# telem_board.net
KiCad netlist of a schematic drawn in EAGLE
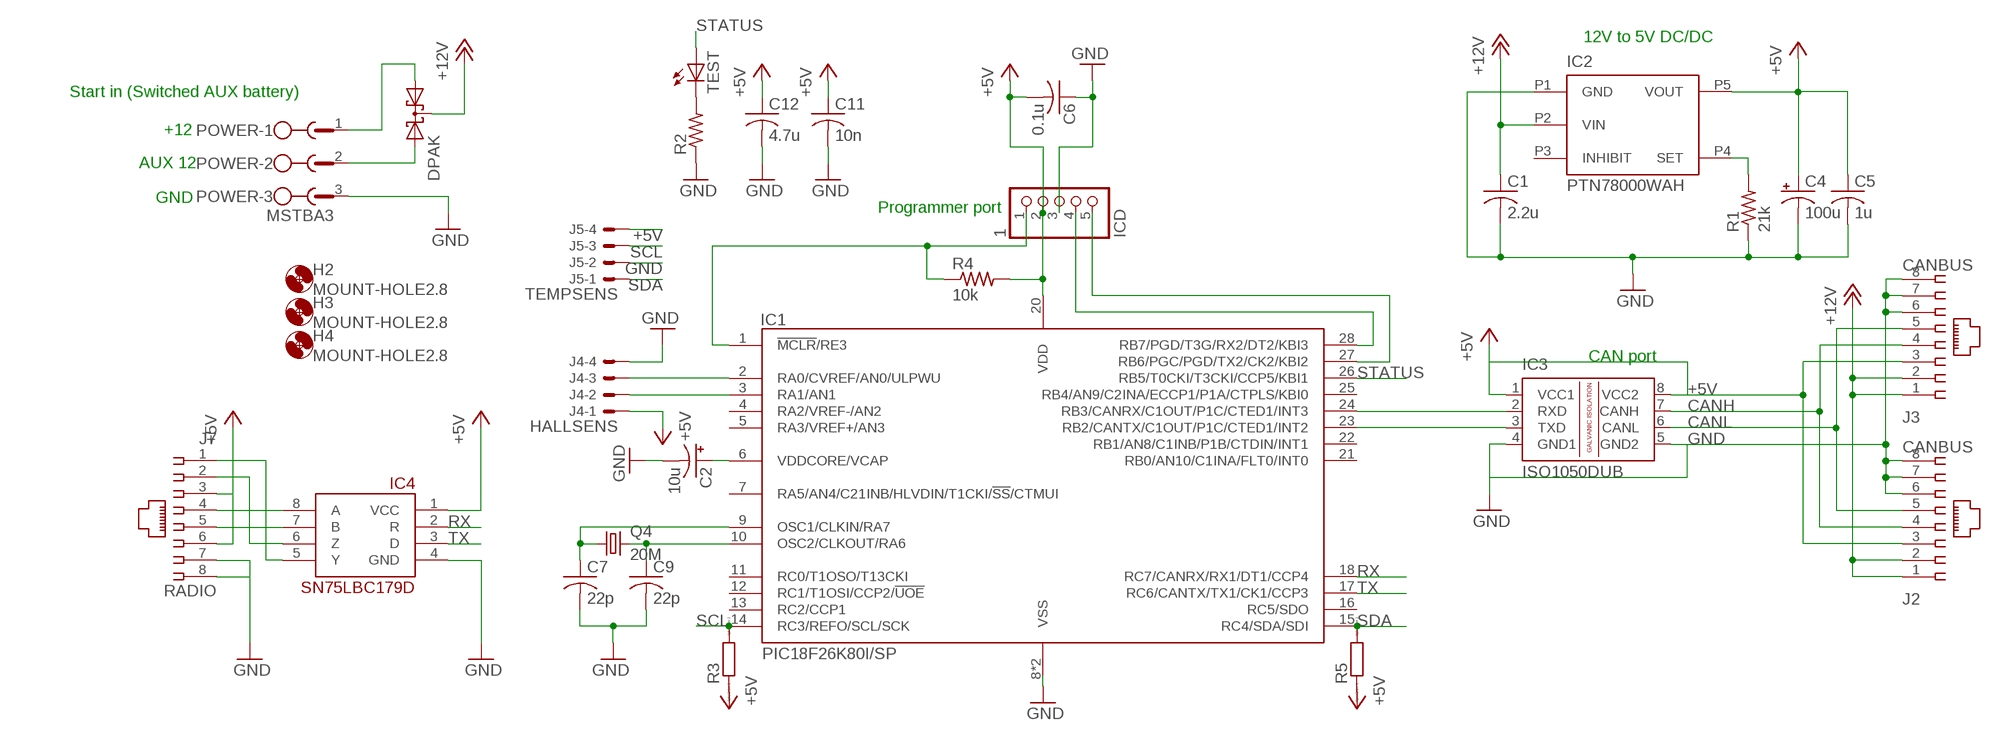
[diagram p0: schematic, sheet 1]

(export (version "E")
  (design (tool "Eeschema 10.0.6"))
  (components
    (comp (ref "1")
      (value "ICD")
      (footprint "eagle-import:1X05")
      (libsource (lib "eagle-import") (part "PINHD-1X5"))
    )
    (comp (ref "C1")
      (value "2.2u")
      (footprint "eagle-import:C1206")
      (libsource (lib "eagle-import") (part "C-USC1206"))
    )
    (comp (ref "C2")
      (value "10u")
      (footprint "eagle-import:TT2D4")
      (libsource (lib "eagle-import") (part "CPOL-USTT2D4"))
    )
    (comp (ref "C4")
      (value "100u")
      (footprint "eagle-import:SMC_D")
      (libsource (lib "eagle-import") (part "CPOL-USSMCD"))
    )
    (comp (ref "C5")
      (value "1u")
      (footprint "eagle-import:C0805")
      (libsource (lib "eagle-import") (part "C-USC0805"))
    )
    (comp (ref "C6")
      (value "0.1u")
      (footprint "eagle-import:C0805")
      (libsource (lib "eagle-import") (part "C-USC0805"))
    )
    (comp (ref "C7")
      (value "22p")
      (footprint "eagle-import:C0805")
      (libsource (lib "eagle-import") (part "C-USC0805"))
    )
    (comp (ref "C9")
      (value "22p")
      (footprint "eagle-import:C0805")
      (libsource (lib "eagle-import") (part "C-USC0805"))
    )
    (comp (ref "C11")
      (value "10n")
      (footprint "eagle-import:C0805")
      (libsource (lib "eagle-import") (part "resistor_C-USC0805"))
    )
    (comp (ref "C12")
      (value "4.7u")
      (footprint "eagle-import:C0805")
      (libsource (lib "eagle-import") (part "resistor_C-USC0805"))
    )
    (comp (ref "DPAK")
      (value "DIODE_2SCHOTTKY-DPAK")
      (footprint "eagle-import:DPAK")
      (libsource (lib "eagle-import") (part "DIODE_2SCHOTTKY-DPAK"))
    )
    (comp (ref "H2")
      (value "MOUNT-HOLE2.8")
      (footprint "eagle-import:2,8")
      (libsource (lib "eagle-import") (part "MOUNT-HOLE2.8"))
    )
    (comp (ref "H3")
      (value "MOUNT-HOLE2.8")
      (footprint "eagle-import:2,8")
      (libsource (lib "eagle-import") (part "MOUNT-HOLE2.8"))
    )
    (comp (ref "H4")
      (value "MOUNT-HOLE2.8")
      (footprint "eagle-import:2,8")
      (libsource (lib "eagle-import") (part "MOUNT-HOLE2.8"))
    )
    (comp (ref "IC1")
      (value "PIC18F26K80I/SP")
      (footprint "eagle-import:DIL28_3")
      (libsource (lib "eagle-import") (part "PIC18F26K80I/SP"))
    )
    (comp (ref "IC2")
      (value "PTN78000WAH")
      (footprint "eagle-import:PTN78000")
      (libsource (lib "eagle-import") (part "PTN78000WAH"))
    )
    (comp (ref "IC3")
      (value "ISO1050DUB")
      (footprint "eagle-import:DUB-R-PDSO-G8")
      (fields (field (name "MPN") "ISO1050DUBR"))
      (libsource (lib "eagle-import") (part "ISO1050DUB"))
    )
    (comp (ref "IC4")
      (value "SN75LBC179D")
      (footprint "eagle-import:SO08")
      (libsource (lib "eagle-import") (part "SN75LBC179D"))
    )
    (comp (ref "J2")
      (value "CANBUS")
      (footprint "eagle-import:215877-7")
      (libsource (lib "eagle-import") (part "215877-7"))
    )
    (comp (ref "J3")
      (value "CANBUS")
      (footprint "eagle-import:215877-7")
      (libsource (lib "eagle-import") (part "215877-7"))
    )
    (comp (ref "J4")
      (value "HALLSENS")
      (footprint "eagle-import:6410-04")
      (libsource (lib "eagle-import") (part "22-?-0427-2041"))
    )
    (comp (ref "J5")
      (value "TEMPSENS")
      (footprint "eagle-import:6410-04")
      (libsource (lib "eagle-import") (part "22-?-0427-2041"))
    )
    (comp (ref "J7")
      (value "RADIO")
      (footprint "eagle-import:215877-7")
      (libsource (lib "eagle-import") (part "215877-7"))
    )
    (comp (ref "POWER")
      (value "MSTBA3")
      (footprint "eagle-import:MSTBA3")
      (fields (field (name "MF") "FARNELL") (field (name "MPN") "1757255"))
      (libsource (lib "eagle-import") (part "MSTBA3"))
    )
    (comp (ref "Q4")
      (value "20M")
      (footprint "eagle-import:HC49_S")
      (libsource (lib "eagle-import") (part "CRYSTALHC49S"))
    )
    (comp (ref "R1")
      (value "21k")
      (footprint "eagle-import:R0805")
      (libsource (lib "eagle-import") (part "rcl_R-US_R0805"))
    )
    (comp (ref "R2")
      (value "R-US_R0805")
      (footprint "eagle-import:R0805")
      (libsource (lib "eagle-import") (part "R-US_R0805"))
    )
    (comp (ref "R3") (value "R") (footprint "eagle-import:R0805") (libsource (lib "eagle-import") (part "R")))
    (comp (ref "R4")
      (value "10k")
      (footprint "eagle-import:R0805")
      (libsource (lib "eagle-import") (part "rcl_R-US_R0805"))
    )
    (comp (ref "R5") (value "R") (footprint "eagle-import:R0805") (libsource (lib "eagle-import") (part "R")))
    (comp (ref "TEST")
      (value "LEDCHIP-LED0805")
      (footprint "eagle-import:CHIP-LED0805")
      (libsource (lib "eagle-import") (part "LEDCHIP-LED0805"))
    )
  )
  (nets
    (net (code "1") (name "+5V") (class "Default")
      (node (ref "1") (pin "2") (pinfunction "2_2") (pintype "passive"))
      (node (ref "C11") (pin "1") (pinfunction "1_1") (pintype "passive"))
      (node (ref "C12") (pin "1") (pinfunction "1_1") (pintype "passive"))
      (node (ref "C4") (pin "+") (pinfunction "+_+") (pintype "passive"))
      (node (ref "C5") (pin "1") (pinfunction "1_1") (pintype "passive"))
      (node (ref "C6") (pin "2") (pinfunction "2_2") (pintype "passive"))
      (node (ref "IC1") (pin "20") (pinfunction "VDD_20") (pintype "power_in"))
      (node (ref "IC2") (pin "P5") (pinfunction "VOUT_P5") (pintype "power_in"))
      (node (ref "IC3") (pin "1") (pinfunction "VCC1_1") (pintype "input"))
      (node (ref "IC3") (pin "8") (pinfunction "VCC2_8") (pintype "input"))
      (node (ref "IC4") (pin "1") (pinfunction "VCC_1") (pintype "power_in"))
      (node (ref "J2") (pin "3") (pinfunction "3_3") (pintype "passive"))
      (node (ref "J3") (pin "3") (pinfunction "3_3") (pintype "passive"))
      (node (ref "J4") (pin "1") (pinfunction "S_1") (pintype "passive"))
      (node (ref "J5") (pin "4") (pinfunction "S_4") (pintype "passive"))
      (node (ref "J7") (pin "3") (pinfunction "3_3") (pintype "passive"))
      (node (ref "J7") (pin "6") (pinfunction "6_6") (pintype "passive"))
      (node (ref "R3") (pin "1") (pinfunction "1_1") (pintype "passive"))
      (node (ref "R4") (pin "2") (pinfunction "2_2") (pintype "passive"))
      (node (ref "R5") (pin "1") (pinfunction "1_1") (pintype "passive"))
    )
    (net (code "2") (name "+12V") (class "Default")
      (node (ref "C1") (pin "1") (pinfunction "1_1") (pintype "passive"))
      (node (ref "DPAK") (pin "3") (pinfunction "C_3") (pintype "passive"))
      (node (ref "IC2") (pin "P2") (pinfunction "VIN_P2") (pintype "power_in"))
      (node (ref "J2") (pin "1") (pinfunction "1_1") (pintype "passive"))
      (node (ref "J2") (pin "2") (pinfunction "2_2") (pintype "passive"))
      (node (ref "J3") (pin "1") (pinfunction "1_1") (pintype "passive"))
      (node (ref "J3") (pin "2") (pinfunction "2_2") (pintype "passive"))
    )
    (net (code "3") (name "/CANH") (class "Default")
      (node (ref "IC3") (pin "7") (pinfunction "CANH_7") (pintype "input"))
      (node (ref "J2") (pin "4") (pinfunction "4_4") (pintype "passive"))
      (node (ref "J3") (pin "4") (pinfunction "4_4") (pintype "passive"))
    )
    (net (code "4") (name "/CANL") (class "Default")
      (node (ref "IC3") (pin "6") (pinfunction "CANL_6") (pintype "input"))
      (node (ref "J2") (pin "5") (pinfunction "5_5") (pintype "passive"))
      (node (ref "J3") (pin "5") (pinfunction "5_5") (pintype "passive"))
    )
    (net (code "5") (name "/RX") (class "Default")
      (node (ref "IC1") (pin "18") (pinfunction "RC7/CANRX/RX1/DT1/CCP4_18") (pintype "bidirectional"))
      (node (ref "IC4") (pin "2") (pinfunction "R_2") (pintype "output"))
    )
    (net (code "6") (name "/SCL") (class "Default")
      (node (ref "IC1") (pin "14") (pinfunction "RC3/REFO/SCL/SCK_14") (pintype "bidirectional"))
      (node (ref "J5") (pin "3") (pinfunction "S_3") (pintype "passive"))
      (node (ref "R3") (pin "2") (pinfunction "2_2") (pintype "passive"))
    )
    (net (code "7") (name "/SDA") (class "Default")
      (node (ref "IC1") (pin "15") (pinfunction "RC4/SDA/SDI_15") (pintype "bidirectional"))
      (node (ref "J5") (pin "1") (pinfunction "S_1") (pintype "passive"))
      (node (ref "R5") (pin "2") (pinfunction "2_2") (pintype "passive"))
    )
    (net (code "8") (name "/STATUS") (class "Default")
      (node (ref "IC1") (pin "26") (pinfunction "RB5/T0CKI/T3CKI/CCP5/KBI1_26") (pintype "bidirectional"))
      (node (ref "TEST") (pin "A") (pinfunction "A_A") (pintype "passive"))
    )
    (net (code "9") (name "/TX") (class "Default")
      (node (ref "IC1") (pin "17") (pinfunction "RC6/CANTX/TX1/CK1/CCP3_17") (pintype "bidirectional"))
      (node (ref "IC4") (pin "3") (pinfunction "D_3") (pintype "input"))
    )
    (net (code "10") (name "GND") (class "Default")
      (node (ref "1") (pin "3") (pinfunction "3_3") (pintype "passive"))
      (node (ref "C1") (pin "2") (pinfunction "2_2") (pintype "passive"))
      (node (ref "C11") (pin "2") (pinfunction "2_2") (pintype "passive"))
      (node (ref "C12") (pin "2") (pinfunction "2_2") (pintype "passive"))
      (node (ref "C2") (pin "-") (pinfunction "-_-") (pintype "passive"))
      (node (ref "C4") (pin "-") (pinfunction "-_-") (pintype "passive"))
      (node (ref "C5") (pin "2") (pinfunction "2_2") (pintype "passive"))
      (node (ref "C6") (pin "1") (pinfunction "1_1") (pintype "passive"))
      (node (ref "C7") (pin "2") (pinfunction "2_2") (pintype "passive"))
      (node (ref "C9") (pin "2") (pinfunction "2_2") (pintype "passive"))
      (node (ref "IC1") (pin "19") (pinfunction "VSS_19") (pintype "power_in"))
      (node (ref "IC1") (pin "8") (pinfunction "VSS_8") (pintype "power_in"))
      (node (ref "IC2") (pin "P1") (pinfunction "GND_P1") (pintype "power_in"))
      (node (ref "IC3") (pin "4") (pinfunction "GND1_4") (pintype "input"))
      (node (ref "IC3") (pin "5") (pinfunction "GND2_5") (pintype "input"))
      (node (ref "IC4") (pin "4") (pinfunction "GND_4") (pintype "power_in"))
      (node (ref "J2") (pin "6") (pinfunction "6_6") (pintype "passive"))
      (node (ref "J2") (pin "7") (pinfunction "7_7") (pintype "passive"))
      (node (ref "J2") (pin "8") (pinfunction "8_8") (pintype "passive"))
      (node (ref "J3") (pin "6") (pinfunction "6_6") (pintype "passive"))
      (node (ref "J3") (pin "7") (pinfunction "7_7") (pintype "passive"))
      (node (ref "J3") (pin "8") (pinfunction "8_8") (pintype "passive"))
      (node (ref "J4") (pin "4") (pinfunction "S_4") (pintype "passive"))
      (node (ref "J5") (pin "2") (pinfunction "S_2") (pintype "passive"))
      (node (ref "J7") (pin "7") (pinfunction "7_7") (pintype "passive"))
      (node (ref "J7") (pin "8") (pinfunction "8_8") (pintype "passive"))
      (node (ref "POWER") (pin "3") (pinfunction "1_3") (pintype "passive"))
      (node (ref "R1") (pin "1") (pinfunction "1_1") (pintype "passive"))
      (node (ref "R2") (pin "1") (pinfunction "1_1") (pintype "passive"))
    )
    (net (code "11") (name "Net-(DPAK-A1)") (class "Default")
      (node (ref "DPAK") (pin "1") (pinfunction "A1_1") (pintype "passive"))
      (node (ref "POWER") (pin "1") (pinfunction "1_1") (pintype "passive"))
    )
    (net (code "12") (name "Net-(DPAK-A2)") (class "Default")
      (node (ref "DPAK") (pin "2") (pinfunction "A2_2") (pintype "passive"))
      (node (ref "POWER") (pin "2") (pinfunction "1_2") (pintype "passive"))
    )
    (net (code "13") (name "Net-(IC1-OSC1{slash}CLKIN{slash}RA7)") (class "Default")
      (node (ref "C7") (pin "1") (pinfunction "1_1") (pintype "passive"))
      (node (ref "IC1") (pin "9") (pinfunction "OSC1/CLKIN/RA7_9") (pintype "bidirectional"))
      (node (ref "Q4") (pin "1") (pinfunction "1_1") (pintype "passive"))
    )
    (net (code "14") (name "Net-(IC1-OSC2{slash}CLKOUT{slash}RA6)") (class "Default")
      (node (ref "C9") (pin "1") (pinfunction "1_1") (pintype "passive"))
      (node (ref "IC1") (pin "10") (pinfunction "OSC2/CLKOUT/RA6_10") (pintype "bidirectional"))
      (node (ref "Q4") (pin "2") (pinfunction "2_2") (pintype "passive"))
    )
    (net (code "15") (name "Net-(IC1-RA0{slash}CVREF{slash}AN0{slash}ULPWU)") (class "Default")
      (node (ref "IC1") (pin "2") (pinfunction "RA0/CVREF/AN0/ULPWU_2") (pintype "bidirectional"))
      (node (ref "J4") (pin "3") (pinfunction "S_3") (pintype "passive"))
    )
    (net (code "16") (name "Net-(IC1-RA1{slash}AN1)") (class "Default")
      (node (ref "IC1") (pin "3") (pinfunction "RA1/AN1_3") (pintype "bidirectional"))
      (node (ref "J4") (pin "2") (pinfunction "S_2") (pintype "passive"))
    )
    (net (code "17") (name "Net-(IC1-RB2{slash}CANTX{slash}C1OUT{slash}P1C{slash}CTED1{slash}INT2)") (class "Default")
      (node (ref "IC1") (pin "23") (pinfunction "RB2/CANTX/C1OUT/P1C/CTED1/INT2_23") (pintype "bidirectional"))
      (node (ref "IC3") (pin "3") (pinfunction "TXD_3") (pintype "input"))
    )
    (net (code "18") (name "Net-(IC1-RB3{slash}CANRX{slash}C1OUT{slash}P1C{slash}CTED1{slash}INT3)") (class "Default")
      (node (ref "IC1") (pin "24") (pinfunction "RB3/CANRX/C1OUT/P1C/CTED1/INT3_24") (pintype "bidirectional"))
      (node (ref "IC3") (pin "2") (pinfunction "RXD_2") (pintype "input"))
    )
    (net (code "19") (name "Net-(IC1-RB6{slash}PGC{slash}PGD{slash}TX2{slash}CK2{slash}KBI2)") (class "Default")
      (node (ref "1") (pin "5") (pinfunction "5_5") (pintype "passive"))
      (node (ref "IC1") (pin "27") (pinfunction "RB6/PGC/PGD/TX2/CK2/KBI2_27") (pintype "bidirectional"))
    )
    (net (code "20") (name "Net-(IC1-RB7{slash}PGD{slash}T3G{slash}RX2{slash}DT2{slash}KBI3)") (class "Default")
      (node (ref "1") (pin "4") (pinfunction "4_4") (pintype "passive"))
      (node (ref "IC1") (pin "28") (pinfunction "RB7/PGD/T3G/RX2/DT2/KBI3_28") (pintype "bidirectional"))
    )
    (net (code "21") (name "Net-(IC1-VDDCORE{slash}VCAP)") (class "Default")
      (node (ref "C2") (pin "+") (pinfunction "+_+") (pintype "passive"))
      (node (ref "IC1") (pin "6") (pinfunction "VDDCORE/VCAP_6") (pintype "bidirectional"))
    )
    (net (code "22") (name "Net-(IC1-~{MCLR}{slash}RE3)") (class "Default")
      (node (ref "1") (pin "1") (pinfunction "1_1") (pintype "passive"))
      (node (ref "IC1") (pin "1") (pinfunction "~{MCLR}/RE3_1") (pintype "input"))
      (node (ref "R4") (pin "1") (pinfunction "1_1") (pintype "passive"))
    )
    (net (code "23") (name "Net-(IC2-SET)") (class "Default")
      (node (ref "IC2") (pin "P4") (pinfunction "SET_P4") (pintype "bidirectional"))
      (node (ref "R1") (pin "2") (pinfunction "2_2") (pintype "passive"))
    )
    (net (code "24") (name "Net-(IC4-A)") (class "Default")
      (node (ref "IC4") (pin "8") (pinfunction "A_8") (pintype "input"))
      (node (ref "J7") (pin "4") (pinfunction "4_4") (pintype "passive"))
    )
    (net (code "25") (name "Net-(IC4-B)") (class "Default")
      (node (ref "IC4") (pin "7") (pinfunction "B_7") (pintype "input"))
      (node (ref "J7") (pin "5") (pinfunction "5_5") (pintype "passive"))
    )
    (net (code "26") (name "Net-(IC4-Y)") (class "Default")
      (node (ref "IC4") (pin "5") (pinfunction "Y_5") (pintype "output"))
      (node (ref "J7") (pin "1") (pinfunction "1_1") (pintype "passive"))
    )
    (net (code "27") (name "Net-(IC4-Z)") (class "Default")
      (node (ref "IC4") (pin "6") (pinfunction "Z_6") (pintype "output"))
      (node (ref "J7") (pin "2") (pinfunction "2_2") (pintype "passive"))
    )
    (net (code "28") (name "Net-(R2-Pad2)") (class "Default")
      (node (ref "R2") (pin "2") (pinfunction "2_2") (pintype "passive"))
      (node (ref "TEST") (pin "C") (pinfunction "C_C") (pintype "passive"))
    )
    (net (code "29") (name "unconnected-(IC1-RA2{slash}VREF-{slash}AN2-Pad4)") (class "Default")
      (node (ref "IC1") (pin "4") (pinfunction "RA2/VREF-/AN2_4") (pintype "bidirectional"))
    )
    (net (code "30") (name "unconnected-(IC1-RA3{slash}VREF+{slash}AN3-Pad5)") (class "Default")
      (node (ref "IC1") (pin "5") (pinfunction "RA3/VREF+/AN3_5") (pintype "bidirectional"))
    )
    (net (code "31") (name "unconnected-(IC1-RA5{slash}AN4{slash}C21INB{slash}HLVDIN{slash}T1CKI{slash}~{SS}{slash}CTMUI-Pad7)") (class "Default")
      (node (ref "IC1") (pin "7") (pinfunction "RA5/AN4/C21INB/HLVDIN/T1CKI/~{SS}/CTMUI_7") (pintype "bidirectional"))
    )
    (net (code "32") (name "unconnected-(IC1-RB0{slash}AN10{slash}C1INA{slash}FLT0{slash}INT0-Pad21)") (class "Default")
      (node (ref "IC1") (pin "21") (pinfunction "RB0/AN10/C1INA/FLT0/INT0_21") (pintype "bidirectional"))
    )
    (net (code "33") (name "unconnected-(IC1-RB1{slash}AN8{slash}C1INB{slash}P1B{slash}CTDIN{slash}INT1-Pad22)") (class "Default")
      (node (ref "IC1") (pin "22") (pinfunction "RB1/AN8/C1INB/P1B/CTDIN/INT1_22") (pintype "bidirectional"))
    )
    (net (code "34") (name "unconnected-(IC1-RB4{slash}AN9{slash}C2INA{slash}ECCP1{slash}P1A{slash}CTPLS{slash}KBI0-Pad25)") (class "Default")
      (node (ref "IC1") (pin "25") (pinfunction "RB4/AN9/C2INA/ECCP1/P1A/CTPLS/KBI0_25") (pintype "bidirectional"))
    )
    (net (code "35") (name "unconnected-(IC1-RC0{slash}T1OSO{slash}T13CKI-Pad11)") (class "Default")
      (node (ref "IC1") (pin "11") (pinfunction "RC0/T1OSO/T13CKI_11") (pintype "bidirectional"))
    )
    (net (code "36") (name "unconnected-(IC1-RC1{slash}T1OSI{slash}CCP2{slash}~{UOE}-Pad12)") (class "Default")
      (node (ref "IC1") (pin "12") (pinfunction "RC1/T1OSI/CCP2/~{UOE}_12") (pintype "bidirectional"))
    )
    (net (code "37") (name "unconnected-(IC1-RC2{slash}CCP1-Pad13)") (class "Default")
      (node (ref "IC1") (pin "13") (pinfunction "RC2/CCP1_13") (pintype "bidirectional"))
    )
    (net (code "38") (name "unconnected-(IC1-RC5{slash}SDO-Pad16)") (class "Default")
      (node (ref "IC1") (pin "16") (pinfunction "RC5/SDO_16") (pintype "bidirectional"))
    )
    (net (code "39") (name "unconnected-(IC2-INHIBIT-PadP3)") (class "Default")
      (node (ref "IC2") (pin "P3") (pinfunction "INHIBIT_P3") (pintype "bidirectional"))
    )
  )
)
